# KC_Input_VAS_Schematic_v0_21.net
KiCad netlist of a schematic drawn in Altium Designer
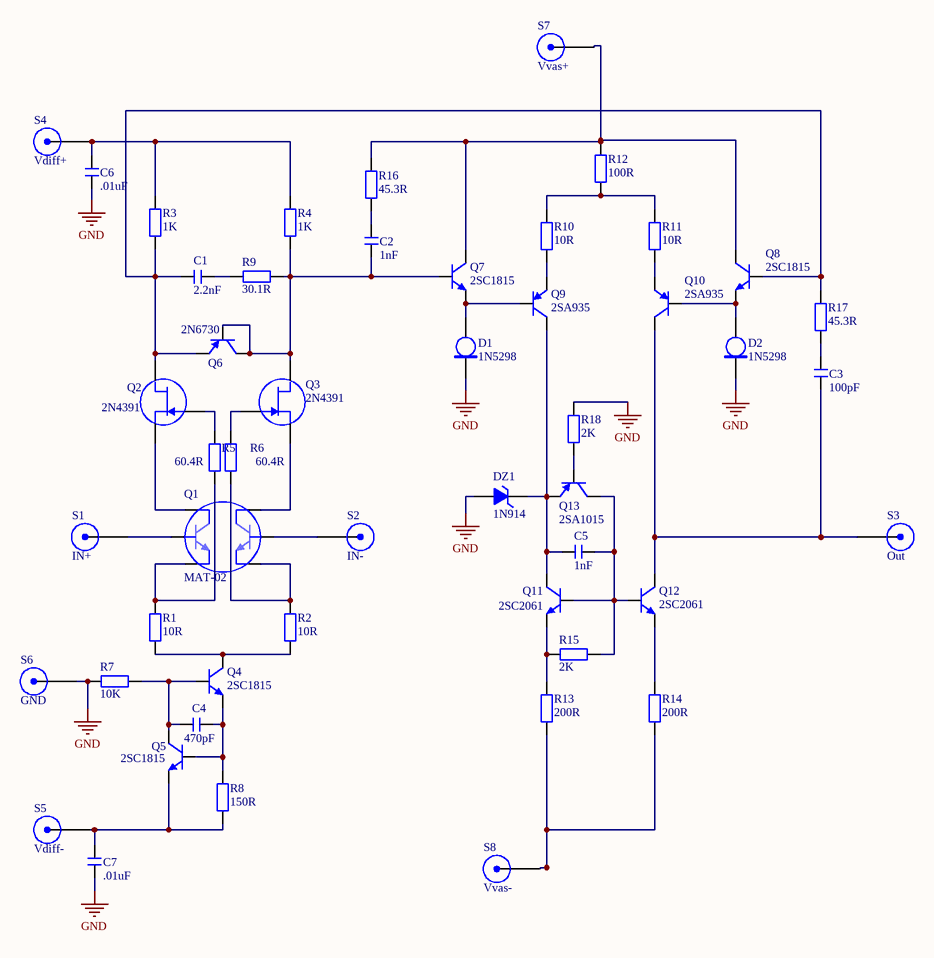
[diagram p0: KC_Input_VAS_Schematic_v0.21.SchDoc]

(export (version "E")
  (design (tool "Eeschema 10.0.6"))
  (components
    (comp (ref "C1")
      (value "2.2nF")
      (footprint "CBB 6.3*6.3*5")
      (description "CBB电容")
      (fields (field (name "版权归属") "源创客"))
      (libsource (lib "电阻-电容-电感") (part "C-CBB"))
    )
    (comp (ref "C2")
      (value "1nF")
      (footprint "CBB 6.3*6.3*5")
      (description "CBB电容")
      (fields (field (name "版权归属") "源创客"))
      (libsource (lib "电阻-电容-电感") (part "C-CBB"))
    )
    (comp (ref "C3")
      (value "100pF")
      (footprint "CBB 6.3*6.3*5")
      (description "CBB电容")
      (fields (field (name "版权归属") "源创客"))
      (libsource (lib "电阻-电容-电感") (part "C-CBB"))
    )
    (comp (ref "C4")
      (value "470pF")
      (footprint "CBB 6.3*6.3*5")
      (description "CBB电容")
      (fields (field (name "版权归属") "源创客"))
      (libsource (lib "电阻-电容-电感") (part "C-CBB"))
    )
    (comp (ref "C5")
      (value "1nF")
      (footprint "CBB 6.3*6.3*5")
      (description "CBB电容")
      (fields (field (name "版权归属") "源创客"))
      (libsource (lib "电阻-电容-电感") (part "C-CBB"))
    )
    (comp (ref "C6")
      (value ".01uF")
      (footprint "CBB 6.3*6.3*5")
      (description "CBB电容")
      (fields (field (name "版权归属") "源创客"))
      (libsource (lib "电阻-电容-电感") (part "C-CBB"))
    )
    (comp (ref "C7")
      (value ".01uF")
      (footprint "CBB 6.3*6.3*5")
      (description "CBB电容")
      (fields (field (name "版权归属") "源创客"))
      (libsource (lib "电阻-电容-电感") (part "C-CBB"))
    )
    (comp (ref "D1")
      (value "1N5298")
      (footprint "DO-41V")
      (description "Current Regulator Diodes")
      (libsource (lib "二极管-整流桥") (part "1N5xxx"))
    )
    (comp (ref "D2")
      (value "1N5298")
      (footprint "DO-41V")
      (description "Current Regulator Diodes")
      (libsource (lib "二极管-整流桥") (part "1N5xxx"))
    )
    (comp (ref "DZ1")
      (value "1N914")
      (footprint "DO-41")
      (description "3V/0.5W稳压管")
      (fields (field (name "版权归属") "源创客"))
      (libsource (lib "二极管-整流桥") (part "1N4619"))
    )
    (comp (ref "Q1")
      (value "MAT-02")
      (footprint "DIP-8")
      (description "孪生对管-NPN型 40V/20ma")
      (libsource (lib "三极管") (part "MAT-02"))
    )
    (comp (ref "Q2")
      (value "2N4391")
      (footprint "TO-18_SMALLHOLE")
      (description "N沟道JFET开关管 40V/150ma")
      (libsource (lib "场效应管") (part "2N4391"))
    )
    (comp (ref "Q3")
      (value "2N4391")
      (footprint "TO-18_SMALLHOLE")
      (description "N沟道JFET开关管 40V/150ma")
      (libsource (lib "场效应管") (part "2N4391"))
    )
    (comp (ref "Q4")
      (value "2SC1815")
      (footprint "TO92A_SmallHole")
      (description "音频放大-NPN型")
      (libsource (lib "三极管") (part "2SC1815"))
    )
    (comp (ref "Q5")
      (value "2SC1815")
      (footprint "TO92A_SmallHole")
      (description "音频放大-NPN型")
      (libsource (lib "三极管") (part "2SC1815"))
    )
    (comp (ref "Q6")
      (value "2N6730")
      (footprint "TO92A_SmallHole")
      (description "中功率放大-PNP型")
      (libsource (lib "三极管") (part "2N6728/6729/6730"))
    )
    (comp (ref "Q7")
      (value "2SC1815")
      (footprint "TO92A_SmallHole")
      (description "音频放大-NPN型")
      (libsource (lib "三极管") (part "2SC1815"))
    )
    (comp (ref "Q8")
      (value "2SC1815")
      (footprint "TO92A_SmallHole")
      (description "音频放大-NPN型")
      (libsource (lib "三极管") (part "2SC1815"))
    )
    (comp (ref "Q9")
      (value "2SA935")
      (footprint "TO92A_SmallHole")
      (description "音频功放-PNP型 50V/500ma")
      (libsource (lib "三极管") (part "2SA935"))
    )
    (comp (ref "Q10")
      (value "2SA935")
      (footprint "TO92A_SmallHole")
      (description "音频功放-PNP型 50V/500ma")
      (libsource (lib "三极管") (part "2SA935"))
    )
    (comp (ref "Q11")
      (value "2SC2061")
      (footprint "TO92A_SmallHole")
      (description "音频放大-NPN型 50V/500ma")
      (libsource (lib "三极管") (part "2SC2061"))
    )
    (comp (ref "Q12")
      (value "2SC2061")
      (footprint "TO92A_SmallHole")
      (description "音频放大-NPN型 50V/500ma")
      (libsource (lib "三极管") (part "2SC2061"))
    )
    (comp (ref "Q13")
      (value "2SA1015")
      (footprint "TO92A_SmallHole")
      (description "音频放大-PNP型")
      (libsource (lib "三极管") (part "2SA1015"))
    )
    (comp (ref "R1")
      (value "10R")
      (footprint "RS 1/2W-L")
      (description "直插色环电阻")
      (fields (field (name "版权归属") "源创客"))
      (libsource (lib "电阻-电容-电感") (part "R-CRR"))
    )
    (comp (ref "R2")
      (value "10R")
      (footprint "RS 1/2W-L")
      (description "直插色环电阻")
      (fields (field (name "版权归属") "源创客"))
      (libsource (lib "电阻-电容-电感") (part "R-CRR"))
    )
    (comp (ref "R3")
      (value "1K")
      (footprint "RS 1/2W-L")
      (description "直插色环电阻")
      (fields (field (name "版权归属") "源创客"))
      (libsource (lib "电阻-电容-电感") (part "R-CRR"))
    )
    (comp (ref "R4")
      (value "1K")
      (footprint "RS 1/2W-L")
      (description "直插色环电阻")
      (fields (field (name "版权归属") "源创客"))
      (libsource (lib "电阻-电容-电感") (part "R-CRR"))
    )
    (comp (ref "R5")
      (value "60.4R")
      (footprint "RS 1/2W-L")
      (description "直插色环电阻")
      (fields (field (name "版权归属") "源创客"))
      (libsource (lib "电阻-电容-电感") (part "R-CRR"))
    )
    (comp (ref "R6")
      (value "60.4R")
      (footprint "RS 1/2W-L")
      (description "直插色环电阻")
      (fields (field (name "版权归属") "源创客"))
      (libsource (lib "电阻-电容-电感") (part "R-CRR"))
    )
    (comp (ref "R7")
      (value "10K")
      (footprint "RS 1/2W-L")
      (description "直插色环电阻")
      (fields (field (name "版权归属") "源创客"))
      (libsource (lib "电阻-电容-电感") (part "R-CRR"))
    )
    (comp (ref "R8")
      (value "150R")
      (footprint "RS 1/2W-L")
      (description "直插色环电阻")
      (fields (field (name "版权归属") "源创客"))
      (libsource (lib "电阻-电容-电感") (part "R-CRR"))
    )
    (comp (ref "R9")
      (value "30.1R")
      (footprint "RS 1/2W-L")
      (description "直插色环电阻")
      (fields (field (name "版权归属") "源创客"))
      (libsource (lib "电阻-电容-电感") (part "R-CRR"))
    )
    (comp (ref "R10")
      (value "10R")
      (footprint "RS 1/2W-L")
      (description "直插色环电阻")
      (fields (field (name "版权归属") "源创客"))
      (libsource (lib "电阻-电容-电感") (part "R-CRR"))
    )
    (comp (ref "R11")
      (value "10R")
      (footprint "RS 1/2W-L")
      (description "直插色环电阻")
      (fields (field (name "版权归属") "源创客"))
      (libsource (lib "电阻-电容-电感") (part "R-CRR"))
    )
    (comp (ref "R12")
      (value "100R")
      (footprint "RS 1/2W-L")
      (description "直插色环电阻")
      (fields (field (name "版权归属") "源创客"))
      (libsource (lib "电阻-电容-电感") (part "R-CRR"))
    )
    (comp (ref "R13")
      (value "200R")
      (footprint "RS 1/2W-L")
      (description "直插色环电阻")
      (fields (field (name "版权归属") "源创客"))
      (libsource (lib "电阻-电容-电感") (part "R-CRR"))
    )
    (comp (ref "R14")
      (value "200R")
      (footprint "RS 1/2W-L")
      (description "直插色环电阻")
      (fields (field (name "版权归属") "源创客"))
      (libsource (lib "电阻-电容-电感") (part "R-CRR"))
    )
    (comp (ref "R15")
      (value "2K")
      (footprint "RS 1/2W-L")
      (description "直插色环电阻")
      (fields (field (name "版权归属") "源创客"))
      (libsource (lib "电阻-电容-电感") (part "R-CRR"))
    )
    (comp (ref "R16")
      (value "45.3R")
      (footprint "RS 1/2W-L")
      (description "直插色环电阻")
      (fields (field (name "版权归属") "源创客"))
      (libsource (lib "电阻-电容-电感") (part "R-CRR"))
    )
    (comp (ref "R17")
      (value "45.3R")
      (footprint "RS 1/2W-L")
      (description "直插色环电阻")
      (fields (field (name "版权归属") "源创客"))
      (libsource (lib "电阻-电容-电感") (part "R-CRR"))
    )
    (comp (ref "R18")
      (value "2K")
      (footprint "RS 1/2W-L")
      (description "直插色环电阻")
      (fields (field (name "版权归属") "源创客"))
      (libsource (lib "电阻-电容-电感") (part "R-CRR"))
    )
    (comp (ref "S1")
      (value "IN+")
      (footprint "Screw-M2-XS")
      (description "Screw Connector")
      (libsource (lib "Connectors") (part "ScrewConnector"))
    )
    (comp (ref "S2")
      (value "IN-")
      (footprint "Screw-M2-XS")
      (description "Screw Connector")
      (libsource (lib "Connectors") (part "ScrewConnector"))
    )
    (comp (ref "S3")
      (value "Out")
      (footprint "Screw-M2-XS")
      (description "Screw Connector")
      (libsource (lib "Connectors") (part "ScrewConnector"))
    )
    (comp (ref "S4")
      (value "Vdiff+")
      (footprint "Screw-M2-XS")
      (description "Screw Connector")
      (libsource (lib "Connectors") (part "ScrewConnector"))
    )
    (comp (ref "S5")
      (value "Vdiff-")
      (footprint "Screw-M2-XS")
      (description "Screw Connector")
      (libsource (lib "Connectors") (part "ScrewConnector"))
    )
    (comp (ref "S6")
      (value "GND")
      (footprint "Screw-M2-XS")
      (description "Screw Connector")
      (libsource (lib "Connectors") (part "ScrewConnector"))
    )
    (comp (ref "S7")
      (value "Vvas+")
      (footprint "Screw-M2-XS")
      (description "Screw Connector")
      (libsource (lib "Connectors") (part "ScrewConnector"))
    )
    (comp (ref "S8")
      (value "Vvas-")
      (footprint "Screw-M2-XS")
      (description "Screw Connector")
      (libsource (lib "Connectors") (part "ScrewConnector"))
    )
  )
  (nets
    (net (code "1") (name "GND") (class "Default")
      (node (ref "C6") (pin "2") (pinfunction "2_2") (pintype "passive"))
      (node (ref "C7") (pin "1") (pinfunction "1_1") (pintype "passive"))
      (node (ref "D1") (pin "1") (pinfunction "Cathode_1") (pintype "passive"))
      (node (ref "D2") (pin "1") (pinfunction "Cathode_1") (pintype "passive"))
      (node (ref "DZ1") (pin "1") (pinfunction "A_1") (pintype "passive"))
      (node (ref "R18") (pin "2") (pinfunction "2_2") (pintype "passive"))
      (node (ref "R7") (pin "1") (pinfunction "1_1") (pintype "passive"))
      (node (ref "S6") (pin "1") (pinfunction "X_1") (pintype "passive"))
    )
    (net (code "2") (name "Net-(C1-Pad2)") (class "Default")
      (node (ref "C1") (pin "2") (pinfunction "2_2") (pintype "passive"))
      (node (ref "R9") (pin "1") (pinfunction "1_1") (pintype "passive"))
    )
    (net (code "3") (name "Net-(C2-Pad1)") (class "Default")
      (node (ref "C2") (pin "1") (pinfunction "1_1") (pintype "passive"))
      (node (ref "R16") (pin "1") (pinfunction "1_1") (pintype "passive"))
    )
    (net (code "4") (name "Net-(C3-Pad2)") (class "Default")
      (node (ref "C3") (pin "2") (pinfunction "2_2") (pintype "passive"))
      (node (ref "R17") (pin "1") (pinfunction "1_1") (pintype "passive"))
    )
    (net (code "5") (name "Net-(D1-Anode)") (class "Default")
      (node (ref "D1") (pin "2") (pinfunction "Anode_2") (pintype "passive"))
      (node (ref "Q7") (pin "1") (pinfunction "E_1") (pintype "passive"))
      (node (ref "Q9") (pin "3") (pinfunction "B_3") (pintype "passive"))
    )
    (net (code "6") (name "Net-(D2-Anode)") (class "Default")
      (node (ref "D2") (pin "2") (pinfunction "Anode_2") (pintype "passive"))
      (node (ref "Q10") (pin "3") (pinfunction "B_3") (pintype "passive"))
      (node (ref "Q8") (pin "1") (pinfunction "E_1") (pintype "passive"))
    )
    (net (code "7") (name "Net-(DZ1-K)") (class "Default")
      (node (ref "C5") (pin "1") (pinfunction "1_1") (pintype "passive"))
      (node (ref "DZ1") (pin "2") (pinfunction "K_2") (pintype "passive"))
      (node (ref "Q11") (pin "2") (pinfunction "C_2") (pintype "passive"))
      (node (ref "Q13") (pin "1") (pinfunction "E_1") (pintype "passive"))
      (node (ref "Q9") (pin "2") (pinfunction "C_2") (pintype "passive"))
    )
    (net (code "8") (name "Net-(Q1-E-Pad3)") (class "Default")
      (node (ref "Q1") (pin "3") (pinfunction "E_3") (pintype "passive"))
      (node (ref "R1") (pin "2") (pinfunction "2_2") (pintype "passive"))
      (node (ref "R5") (pin "1") (pinfunction "1_1") (pintype "passive"))
    )
    (net (code "9") (name "Net-(Q1-E-Pad5)") (class "Default")
      (node (ref "Q1") (pin "5") (pinfunction "E_5") (pintype "passive"))
      (node (ref "R2") (pin "2") (pinfunction "2_2") (pintype "passive"))
      (node (ref "R6") (pin "1") (pinfunction "1_1") (pintype "passive"))
    )
    (net (code "10") (name "Net-(Q2-D)") (class "Default")
      (node (ref "C1") (pin "1") (pinfunction "1_1") (pintype "passive"))
      (node (ref "Q2") (pin "3") (pinfunction "D_3") (pintype "passive"))
      (node (ref "Q6") (pin "1") (pinfunction "E_1") (pintype "passive"))
      (node (ref "Q8") (pin "3") (pinfunction "B_3") (pintype "passive"))
      (node (ref "R17") (pin "2") (pinfunction "2_2") (pintype "passive"))
      (node (ref "R3") (pin "1") (pinfunction "1_1") (pintype "passive"))
    )
    (net (code "11") (name "Net-(Q2-G)") (class "Default")
      (node (ref "Q2") (pin "2") (pinfunction "G_2") (pintype "passive"))
      (node (ref "R5") (pin "2") (pinfunction "2_2") (pintype "passive"))
    )
    (net (code "12") (name "Net-(Q2-S)") (class "Default")
      (node (ref "Q1") (pin "1") (pinfunction "C_1") (pintype "passive"))
      (node (ref "Q2") (pin "1") (pinfunction "S_1") (pintype "passive"))
    )
    (net (code "13") (name "Net-(Q3-D)") (class "Default")
      (node (ref "C2") (pin "2") (pinfunction "2_2") (pintype "passive"))
      (node (ref "Q3") (pin "3") (pinfunction "D_3") (pintype "passive"))
      (node (ref "Q6") (pin "2") (pinfunction "C_2") (pintype "passive"))
      (node (ref "Q6") (pin "3") (pinfunction "B_3") (pintype "passive"))
      (node (ref "Q7") (pin "3") (pinfunction "B_3") (pintype "passive"))
      (node (ref "R4") (pin "1") (pinfunction "1_1") (pintype "passive"))
      (node (ref "R9") (pin "2") (pinfunction "2_2") (pintype "passive"))
    )
    (net (code "14") (name "Net-(Q3-G)") (class "Default")
      (node (ref "Q3") (pin "2") (pinfunction "G_2") (pintype "passive"))
      (node (ref "R6") (pin "2") (pinfunction "2_2") (pintype "passive"))
    )
    (net (code "15") (name "Net-(Q3-S)") (class "Default")
      (node (ref "Q1") (pin "7") (pinfunction "C_7") (pintype "passive"))
      (node (ref "Q3") (pin "1") (pinfunction "S_1") (pintype "passive"))
    )
    (net (code "16") (name "Net-(Q4-B)") (class "Default")
      (node (ref "C4") (pin "1") (pinfunction "1_1") (pintype "passive"))
      (node (ref "Q4") (pin "3") (pinfunction "B_3") (pintype "passive"))
      (node (ref "Q5") (pin "2") (pinfunction "C_2") (pintype "passive"))
      (node (ref "R7") (pin "2") (pinfunction "2_2") (pintype "passive"))
    )
    (net (code "17") (name "Net-(Q4-C)") (class "Default")
      (node (ref "Q4") (pin "2") (pinfunction "C_2") (pintype "passive"))
      (node (ref "R1") (pin "1") (pinfunction "1_1") (pintype "passive"))
      (node (ref "R2") (pin "1") (pinfunction "1_1") (pintype "passive"))
    )
    (net (code "18") (name "Net-(Q4-E)") (class "Default")
      (node (ref "C4") (pin "2") (pinfunction "2_2") (pintype "passive"))
      (node (ref "Q4") (pin "1") (pinfunction "E_1") (pintype "passive"))
      (node (ref "Q5") (pin "3") (pinfunction "B_3") (pintype "passive"))
      (node (ref "R8") (pin "1") (pinfunction "1_1") (pintype "passive"))
    )
    (net (code "19") (name "Net-(Q5-E)") (class "Default")
      (node (ref "C7") (pin "2") (pinfunction "2_2") (pintype "passive"))
      (node (ref "Q5") (pin "1") (pinfunction "E_1") (pintype "passive"))
      (node (ref "R8") (pin "2") (pinfunction "2_2") (pintype "passive"))
      (node (ref "S5") (pin "1") (pinfunction "X_1") (pintype "passive"))
    )
    (net (code "20") (name "Net-(Q7-C)") (class "Default")
      (node (ref "Q7") (pin "2") (pinfunction "C_2") (pintype "passive"))
      (node (ref "Q8") (pin "2") (pinfunction "C_2") (pintype "passive"))
      (node (ref "R12") (pin "2") (pinfunction "2_2") (pintype "passive"))
      (node (ref "R16") (pin "2") (pinfunction "2_2") (pintype "passive"))
      (node (ref "S7") (pin "1") (pinfunction "X_1") (pintype "passive"))
    )
    (net (code "21") (name "Net-(Q9-E)") (class "Default")
      (node (ref "Q9") (pin "1") (pinfunction "E_1") (pintype "passive"))
      (node (ref "R10") (pin "1") (pinfunction "1_1") (pintype "passive"))
    )
    (net (code "22") (name "Net-(Q10-C)") (class "Default")
      (node (ref "C3") (pin "1") (pinfunction "1_1") (pintype "passive"))
      (node (ref "Q10") (pin "2") (pinfunction "C_2") (pintype "passive"))
      (node (ref "Q12") (pin "2") (pinfunction "C_2") (pintype "passive"))
      (node (ref "S3") (pin "1") (pinfunction "X_1") (pintype "passive"))
    )
    (net (code "23") (name "Net-(Q10-E)") (class "Default")
      (node (ref "Q10") (pin "1") (pinfunction "E_1") (pintype "passive"))
      (node (ref "R11") (pin "1") (pinfunction "1_1") (pintype "passive"))
    )
    (net (code "24") (name "Net-(Q11-B)") (class "Default")
      (node (ref "C5") (pin "2") (pinfunction "2_2") (pintype "passive"))
      (node (ref "Q11") (pin "3") (pinfunction "B_3") (pintype "passive"))
      (node (ref "Q12") (pin "3") (pinfunction "B_3") (pintype "passive"))
      (node (ref "Q13") (pin "2") (pinfunction "C_2") (pintype "passive"))
      (node (ref "R15") (pin "1") (pinfunction "1_1") (pintype "passive"))
    )
    (net (code "25") (name "Net-(Q11-E)") (class "Default")
      (node (ref "Q11") (pin "1") (pinfunction "E_1") (pintype "passive"))
      (node (ref "R13") (pin "2") (pinfunction "2_2") (pintype "passive"))
      (node (ref "R15") (pin "2") (pinfunction "2_2") (pintype "passive"))
    )
    (net (code "26") (name "Net-(Q12-E)") (class "Default")
      (node (ref "Q12") (pin "1") (pinfunction "E_1") (pintype "passive"))
      (node (ref "R14") (pin "2") (pinfunction "2_2") (pintype "passive"))
    )
    (net (code "27") (name "Net-(Q13-B)") (class "Default")
      (node (ref "Q13") (pin "3") (pinfunction "B_3") (pintype "passive"))
      (node (ref "R18") (pin "1") (pinfunction "1_1") (pintype "passive"))
    )
    (net (code "28") (name "Net-(R10-Pad2)") (class "Default")
      (node (ref "R10") (pin "2") (pinfunction "2_2") (pintype "passive"))
      (node (ref "R11") (pin "2") (pinfunction "2_2") (pintype "passive"))
      (node (ref "R12") (pin "1") (pinfunction "1_1") (pintype "passive"))
    )
    (net (code "29") (name "Net-(S1-X)") (class "Default")
      (node (ref "Q1") (pin "2") (pinfunction "B_2") (pintype "passive"))
      (node (ref "S1") (pin "1") (pinfunction "X_1") (pintype "passive"))
    )
    (net (code "30") (name "Net-(S2-X)") (class "Default")
      (node (ref "Q1") (pin "6") (pinfunction "B_6") (pintype "passive"))
      (node (ref "S2") (pin "1") (pinfunction "X_1") (pintype "passive"))
    )
    (net (code "31") (name "Net-(S4-X)") (class "Default")
      (node (ref "C6") (pin "1") (pinfunction "1_1") (pintype "passive"))
      (node (ref "R3") (pin "2") (pinfunction "2_2") (pintype "passive"))
      (node (ref "R4") (pin "2") (pinfunction "2_2") (pintype "passive"))
      (node (ref "S4") (pin "1") (pinfunction "X_1") (pintype "passive"))
    )
    (net (code "32") (name "Net-(S8-X)") (class "Default")
      (node (ref "R13") (pin "1") (pinfunction "1_1") (pintype "passive"))
      (node (ref "R14") (pin "1") (pinfunction "1_1") (pintype "passive"))
      (node (ref "S8") (pin "1") (pinfunction "X_1") (pintype "passive"))
    )
  )
)
